# Own_26650_Board_v1_1_Final_AR.net
KiCad netlist of a schematic drawn in EAGLE
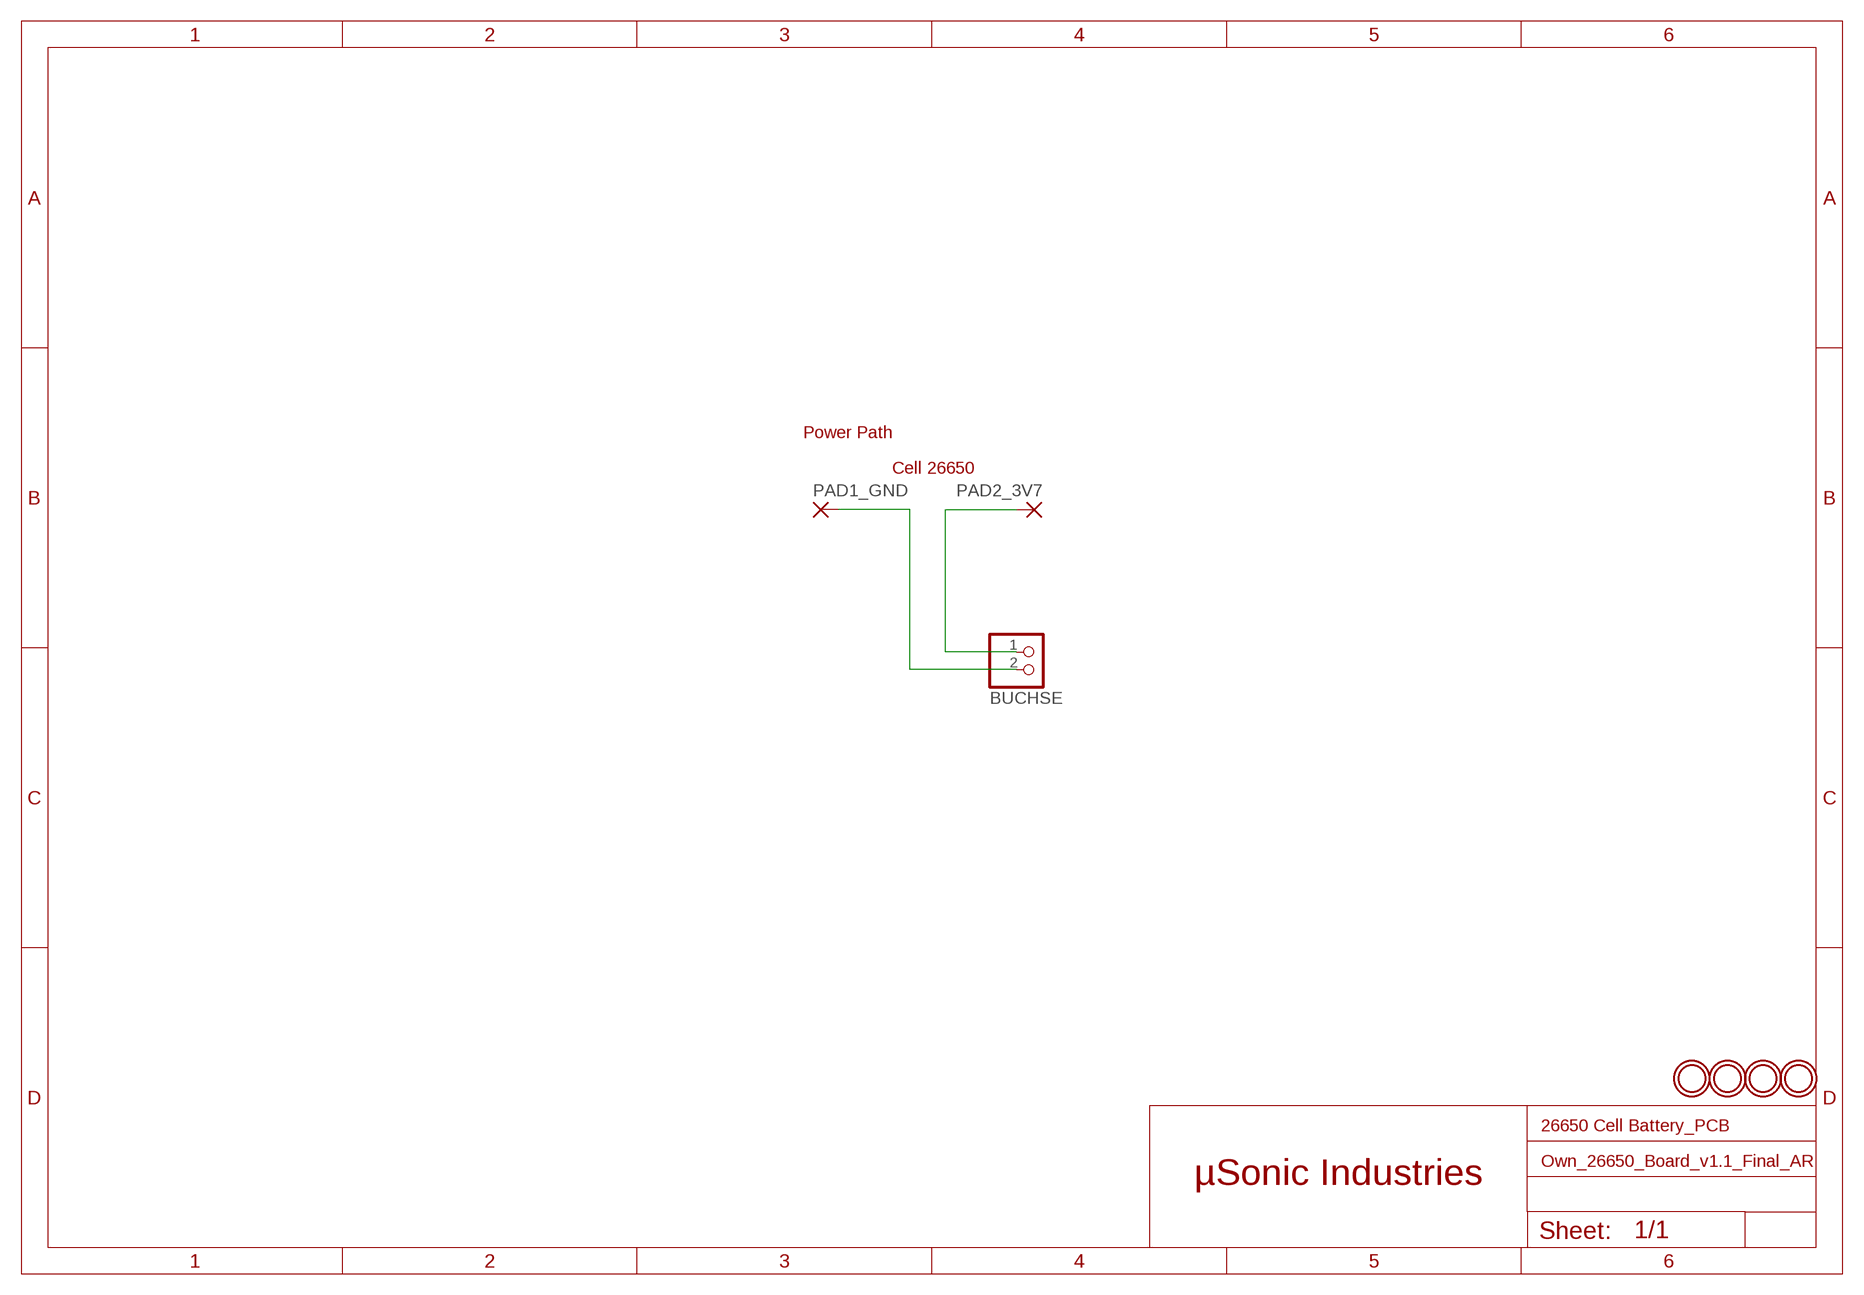
[diagram p0: schematic, sheet 1]

(export (version "E")
  (design (tool "Eeschema 10.0.6"))
  (components
    (comp (ref "BUCHSE")
      (value "JST_2PINOWN")
      (footprint "eagle-import:JST-PH-2-THMOWN")
      (libsource (lib "eagle-import") (part "JST_2PINOWN"))
    )
    (comp (ref "PAD1_GND")
      (value "WIREPADSMDOWN")
      (footprint "eagle-import:OWN")
      (libsource (lib "eagle-import") (part "WIREPADSMDOWN"))
    )
    (comp (ref "PAD2_3V7")
      (value "WIREPADSMDOWN")
      (footprint "eagle-import:OWN")
      (libsource (lib "eagle-import") (part "WIREPADSMDOWN"))
    )
    (comp (ref "U$1")
      (value "MOUNTINGHOLE2.5")
      (footprint "eagle-import:MOUNTINGHOLE_2.5_PLATED")
      (libsource (lib "eagle-import") (part "MOUNTINGHOLE2.5"))
    )
    (comp (ref "U$2")
      (value "MOUNTINGHOLE2.5")
      (footprint "eagle-import:MOUNTINGHOLE_2.5_PLATED")
      (libsource (lib "eagle-import") (part "MOUNTINGHOLE2.5"))
    )
    (comp (ref "U$3")
      (value "MOUNTINGHOLE2.5")
      (footprint "eagle-import:MOUNTINGHOLE_2.5_PLATED")
      (libsource (lib "eagle-import") (part "MOUNTINGHOLE2.5"))
    )
    (comp (ref "U$5")
      (value "MOUNTINGHOLE2.5")
      (footprint "eagle-import:MOUNTINGHOLE_2.5_PLATED")
      (libsource (lib "eagle-import") (part "MOUNTINGHOLE2.5"))
    )
  )
  (nets
    (net (code "1") (name "Net-(BUCHSE-1)") (class "Default")
      (node (ref "BUCHSE") (pin "2") (pinfunction "1_2") (pintype "passive"))
      (node (ref "PAD1_GND") (pin "1") (pinfunction "P_1") (pintype "passive"))
    )
    (net (code "2") (name "Net-(BUCHSE-2)") (class "Default")
      (node (ref "BUCHSE") (pin "1") (pinfunction "2_1") (pintype "passive"))
      (node (ref "PAD2_3V7") (pin "1") (pinfunction "P_1") (pintype "passive"))
    )
  )
)
